# 15_-FPGA_Bank_8_Interface.net
KiCad netlist of a schematic drawn in Altium Designer
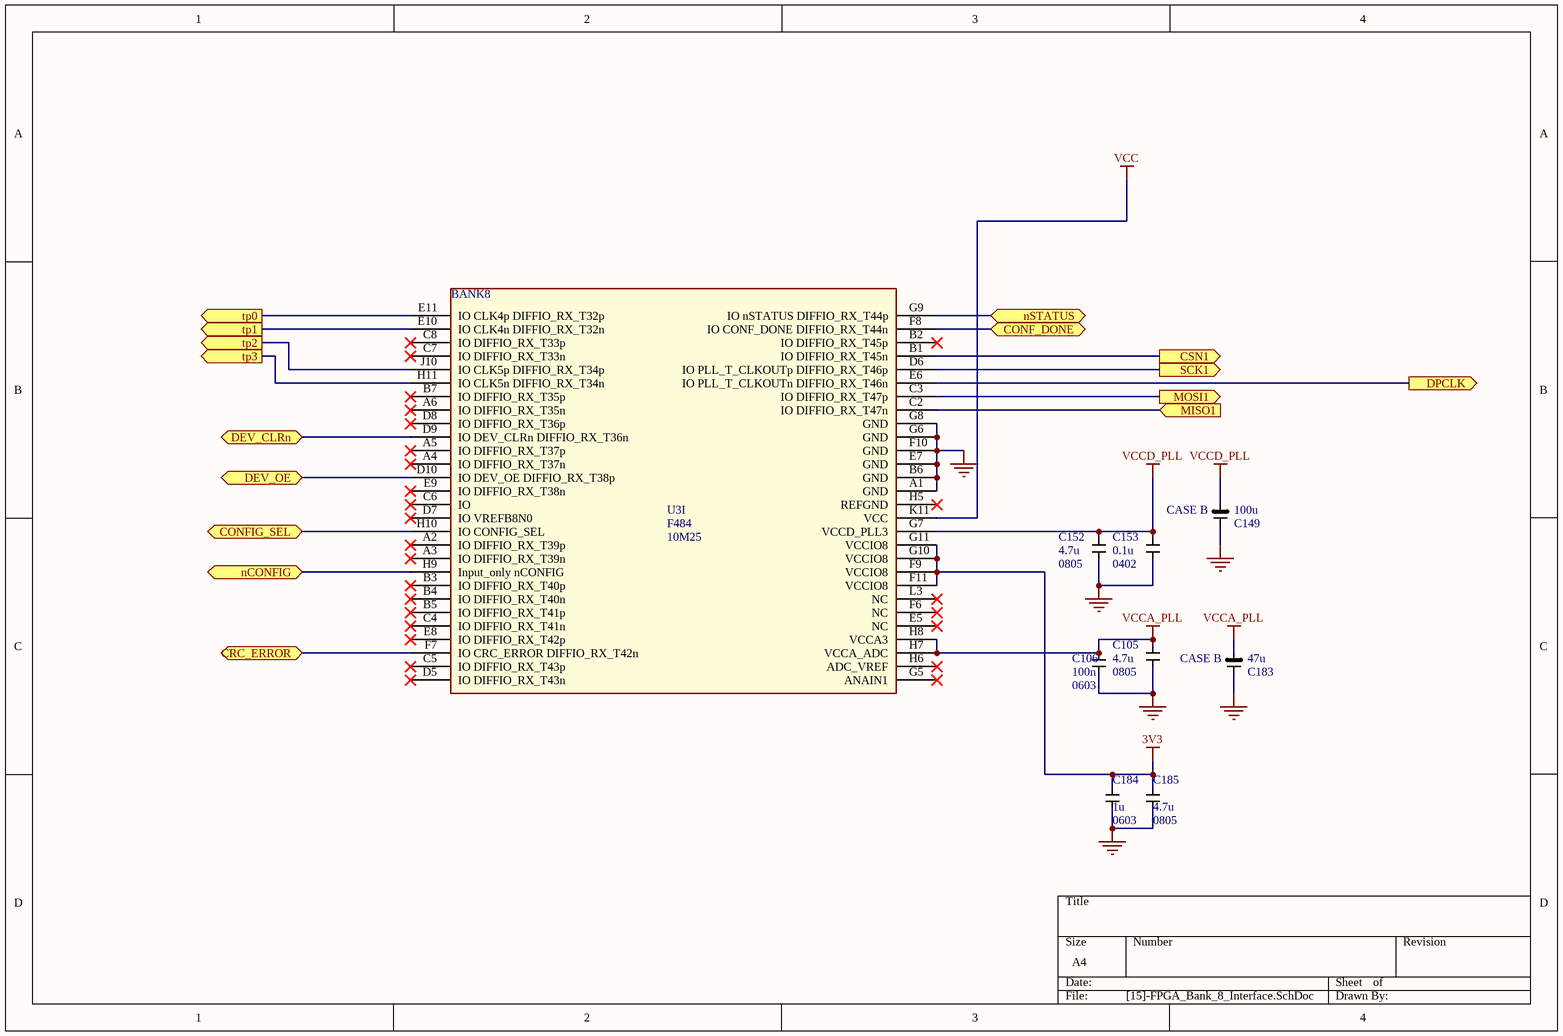
[diagram p0: [15]-FPGA_Bank_8_Interface.SchDoc]

(export (version "E")
  (design (tool "Eeschema 10.0.6"))
  (components
    (comp (ref "C105")
      (value "4.7u")
      (fields (field (name "PCB FOOTPRINT") "0805"))
      (libsource (lib "06031C104KAT2A") (part "Component_1"))
    )
    (comp (ref "C106")
      (value "100n")
      (footprint "*0603")
      (fields (field (name "PCB LAYER:") "0603"))
      (libsource (lib "0603YC105KAT2A") (part "Component_1"))
    )
    (comp (ref "C149")
      (value "100u")
      (footprint "CAPC3529X21N")
      (fields (field (name "CASE") "CASE B"))
      (libsource (lib "TAJB107K006TNJ") (part "Component_1"))
    )
    (comp (ref "C152")
      (value "4.7u")
      (fields (field (name "PCB FOOTPRINT") "0805"))
      (libsource (lib "06031C104KAT2A") (part "Component_1"))
    )
    (comp (ref "C153")
      (value "0.1u")
      (fields (field (name "PCB FOOTPRINT") "0402"))
      (libsource (lib "06031C104KAT2A") (part "Component_1"))
    )
    (comp (ref "C183")
      (value "47u")
      (footprint "CAPC3529X21N")
      (fields (field (name "CASE") "CASE B"))
      (libsource (lib "TAJB107K006TNJ") (part "Component_1"))
    )
    (comp (ref "C184")
      (value "1u")
      (footprint "*0603")
      (fields (field (name "PCB LAYER:") "0603"))
      (libsource (lib "0603YC105KAT2A") (part "Component_1"))
    )
    (comp (ref "C185")
      (value "4.7u")
      (footprint "*CAPC2013X140N")
      (fields (field (name "PCB PACKAGE") "0805"))
      (libsource (lib "08053D475KAT2A") (part "Component_1"))
    )
    (comp (ref "U3")
      (value "10M25")
      (footprint "*BGA484C100P22X22_2300X2300X200N")
      (fields (field (name "PART NO.") "10M25DAF484I7G") (field (name "PACKAGE TYPE") "F484"))
      (libsource (lib "10M25DAF484I7G") (part "Component_1"))
    )
  )
  (nets
    (net (code "1") (name "/CONFIG_SEL") (class "Default")
      (node (ref "U3") (pin "H10") (pinfunction "IO_CONFIG_SEL_H10") (pintype "passive"))
    )
    (net (code "2") (name "/CONF_DONE") (class "Default")
      (node (ref "U3") (pin "F8") (pinfunction "IO_CONF_DONE_DIFFIO_RX_T44n_F8") (pintype "passive"))
    )
    (net (code "3") (name "/CRC_ERROR") (class "Default")
      (node (ref "U3") (pin "F7") (pinfunction "IO_CRC_ERROR_DIFFIO_RX_T42n_F7") (pintype "passive"))
    )
    (net (code "4") (name "/CSN1") (class "Default")
      (node (ref "U3") (pin "B1") (pinfunction "IO_DIFFIO_RX_T45n_B1") (pintype "passive"))
    )
    (net (code "5") (name "/DEV_CLRn") (class "Default")
      (node (ref "U3") (pin "D9") (pinfunction "IO_DEV_CLRn_DIFFIO_RX_T36n_D9") (pintype "passive"))
    )
    (net (code "6") (name "/DEV_OE") (class "Default")
      (node (ref "U3") (pin "D10") (pinfunction "IO_DEV_OE_DIFFIO_RX_T38p_D10") (pintype "passive"))
    )
    (net (code "7") (name "/DPCLK") (class "Default")
      (node (ref "U3") (pin "E6") (pinfunction "IO_PLL_T_CLKOUTn_DIFFIO_RX_T46n_E6") (pintype "passive"))
    )
    (net (code "8") (name "/MISO1") (class "Default")
      (node (ref "U3") (pin "C2") (pinfunction "IO_DIFFIO_RX_T47n_C2") (pintype "passive"))
    )
    (net (code "9") (name "/MOSI1") (class "Default")
      (node (ref "U3") (pin "C3") (pinfunction "IO_DIFFIO_RX_T47p_C3") (pintype "passive"))
    )
    (net (code "10") (name "/SCK1") (class "Default")
      (node (ref "U3") (pin "D6") (pinfunction "IO_PLL_T_CLKOUTp_DIFFIO_RX_T46p_D6") (pintype "passive"))
    )
    (net (code "11") (name "/nCONFIG") (class "Default")
      (node (ref "U3") (pin "H9") (pinfunction "Input_only_nCONFIG_H9") (pintype "passive"))
    )
    (net (code "12") (name "/nSTATUS") (class "Default")
      (node (ref "U3") (pin "G9") (pinfunction "IO_nSTATUS_DIFFIO_RX_T44p_G9") (pintype "passive"))
    )
    (net (code "13") (name "/tp0") (class "Default")
      (node (ref "U3") (pin "E11") (pinfunction "IO_CLK4p_DIFFIO_RX_T32p_E11") (pintype "passive"))
    )
    (net (code "14") (name "/tp1") (class "Default")
      (node (ref "U3") (pin "E10") (pinfunction "IO_CLK4n_DIFFIO_RX_T32n_E10") (pintype "passive"))
    )
    (net (code "15") (name "/tp2") (class "Default")
      (node (ref "U3") (pin "J10") (pinfunction "IO_CLK5p_DIFFIO_RX_T34p_J10") (pintype "passive"))
    )
    (net (code "16") (name "/tp3") (class "Default")
      (node (ref "U3") (pin "H11") (pinfunction "IO_CLK5n_DIFFIO_RX_T34n_H11") (pintype "passive"))
    )
    (net (code "17") (name "3V3") (class "Default")
      (node (ref "C184") (pin "2") (pinfunction "2_2") (pintype "passive"))
      (node (ref "C185") (pin "2") (pinfunction "2_2") (pintype "passive"))
      (node (ref "U3") (pin "F11") (pinfunction "VCCIO8_F11") (pintype "passive"))
      (node (ref "U3") (pin "F9") (pinfunction "VCCIO8_F9") (pintype "passive"))
      (node (ref "U3") (pin "G10") (pinfunction "VCCIO8_G10") (pintype "passive"))
      (node (ref "U3") (pin "G11") (pinfunction "VCCIO8_G11") (pintype "passive"))
    )
    (net (code "18") (name "GND") (class "Default")
      (node (ref "C105") (pin "1") (pinfunction "1_1") (pintype "passive"))
      (node (ref "C106") (pin "1") (pinfunction "1_1") (pintype "passive"))
      (node (ref "C149") (pin "2") (pinfunction "2_2") (pintype "passive"))
      (node (ref "C152") (pin "1") (pinfunction "1_1") (pintype "passive"))
      (node (ref "C153") (pin "1") (pinfunction "1_1") (pintype "passive"))
      (node (ref "C183") (pin "2") (pinfunction "2_2") (pintype "passive"))
      (node (ref "C184") (pin "1") (pinfunction "1_1") (pintype "passive"))
      (node (ref "C185") (pin "1") (pinfunction "1_1") (pintype "passive"))
      (node (ref "U3") (pin "A1") (pinfunction "GND_A1") (pintype "passive"))
      (node (ref "U3") (pin "B6") (pinfunction "GND_B6") (pintype "passive"))
      (node (ref "U3") (pin "E7") (pinfunction "GND_E7") (pintype "passive"))
      (node (ref "U3") (pin "F10") (pinfunction "GND_F10") (pintype "passive"))
      (node (ref "U3") (pin "G6") (pinfunction "GND_G6") (pintype "passive"))
      (node (ref "U3") (pin "G8") (pinfunction "GND_G8") (pintype "passive"))
    )
    (net (code "19") (name "VCC") (class "Default")
      (node (ref "U3") (pin "K11") (pinfunction "VCC_K11") (pintype "passive"))
    )
    (net (code "20") (name "VCCA_PLL") (class "Default")
      (node (ref "C105") (pin "2") (pinfunction "2_2") (pintype "passive"))
      (node (ref "C106") (pin "2") (pinfunction "2_2") (pintype "passive"))
      (node (ref "C183") (pin "1") (pinfunction "1_1") (pintype "passive"))
      (node (ref "U3") (pin "H7") (pinfunction "VCCA_ADC_H7") (pintype "passive"))
      (node (ref "U3") (pin "H8") (pinfunction "VCCA3_H8") (pintype "passive"))
    )
    (net (code "21") (name "VCCD_PLL") (class "Default")
      (node (ref "C149") (pin "1") (pinfunction "1_1") (pintype "passive"))
      (node (ref "C152") (pin "2") (pinfunction "2_2") (pintype "passive"))
      (node (ref "C153") (pin "2") (pinfunction "2_2") (pintype "passive"))
      (node (ref "U3") (pin "G7") (pinfunction "VCCD_PLL3_G7") (pintype "passive"))
    )
    (net (code "22") (name "unconnected-(U3I-ADC_VREF-PadH6)") (class "Default")
      (node (ref "U3") (pin "H6") (pinfunction "ADC_VREF_H6") (pintype "passive+no_connect"))
    )
    (net (code "23") (name "unconnected-(U3I-ANAIN1-PadG5)") (class "Default")
      (node (ref "U3") (pin "G5") (pinfunction "ANAIN1_G5") (pintype "passive+no_connect"))
    )
    (net (code "24") (name "unconnected-(U3I-IO-PadC6)") (class "Default")
      (node (ref "U3") (pin "C6") (pinfunction "IO_C6") (pintype "passive+no_connect"))
    )
    (net (code "25") (name "unconnected-(U3I-IO_DIFFIO_RX_T33n-PadC7)") (class "Default")
      (node (ref "U3") (pin "C7") (pinfunction "IO_DIFFIO_RX_T33n_C7") (pintype "passive+no_connect"))
    )
    (net (code "26") (name "unconnected-(U3I-IO_DIFFIO_RX_T33p-PadC8)") (class "Default")
      (node (ref "U3") (pin "C8") (pinfunction "IO_DIFFIO_RX_T33p_C8") (pintype "passive+no_connect"))
    )
    (net (code "27") (name "unconnected-(U3I-IO_DIFFIO_RX_T35n-PadA6)") (class "Default")
      (node (ref "U3") (pin "A6") (pinfunction "IO_DIFFIO_RX_T35n_A6") (pintype "passive+no_connect"))
    )
    (net (code "28") (name "unconnected-(U3I-IO_DIFFIO_RX_T35p-PadB7)") (class "Default")
      (node (ref "U3") (pin "B7") (pinfunction "IO_DIFFIO_RX_T35p_B7") (pintype "passive+no_connect"))
    )
    (net (code "29") (name "unconnected-(U3I-IO_DIFFIO_RX_T36p-PadD8)") (class "Default")
      (node (ref "U3") (pin "D8") (pinfunction "IO_DIFFIO_RX_T36p_D8") (pintype "passive+no_connect"))
    )
    (net (code "30") (name "unconnected-(U3I-IO_DIFFIO_RX_T37n-PadA4)") (class "Default")
      (node (ref "U3") (pin "A4") (pinfunction "IO_DIFFIO_RX_T37n_A4") (pintype "passive+no_connect"))
    )
    (net (code "31") (name "unconnected-(U3I-IO_DIFFIO_RX_T37p-PadA5)") (class "Default")
      (node (ref "U3") (pin "A5") (pinfunction "IO_DIFFIO_RX_T37p_A5") (pintype "passive+no_connect"))
    )
    (net (code "32") (name "unconnected-(U3I-IO_DIFFIO_RX_T38n-PadE9)") (class "Default")
      (node (ref "U3") (pin "E9") (pinfunction "IO_DIFFIO_RX_T38n_E9") (pintype "passive+no_connect"))
    )
    (net (code "33") (name "unconnected-(U3I-IO_DIFFIO_RX_T39n-PadA3)") (class "Default")
      (node (ref "U3") (pin "A3") (pinfunction "IO_DIFFIO_RX_T39n_A3") (pintype "passive+no_connect"))
    )
    (net (code "34") (name "unconnected-(U3I-IO_DIFFIO_RX_T39p-PadA2)") (class "Default")
      (node (ref "U3") (pin "A2") (pinfunction "IO_DIFFIO_RX_T39p_A2") (pintype "passive+no_connect"))
    )
    (net (code "35") (name "unconnected-(U3I-IO_DIFFIO_RX_T40n-PadB4)") (class "Default")
      (node (ref "U3") (pin "B4") (pinfunction "IO_DIFFIO_RX_T40n_B4") (pintype "passive+no_connect"))
    )
    (net (code "36") (name "unconnected-(U3I-IO_DIFFIO_RX_T40p-PadB3)") (class "Default")
      (node (ref "U3") (pin "B3") (pinfunction "IO_DIFFIO_RX_T40p_B3") (pintype "passive+no_connect"))
    )
    (net (code "37") (name "unconnected-(U3I-IO_DIFFIO_RX_T41n-PadC4)") (class "Default")
      (node (ref "U3") (pin "C4") (pinfunction "IO_DIFFIO_RX_T41n_C4") (pintype "passive+no_connect"))
    )
    (net (code "38") (name "unconnected-(U3I-IO_DIFFIO_RX_T41p-PadB5)") (class "Default")
      (node (ref "U3") (pin "B5") (pinfunction "IO_DIFFIO_RX_T41p_B5") (pintype "passive+no_connect"))
    )
    (net (code "39") (name "unconnected-(U3I-IO_DIFFIO_RX_T42p-PadE8)") (class "Default")
      (node (ref "U3") (pin "E8") (pinfunction "IO_DIFFIO_RX_T42p_E8") (pintype "passive+no_connect"))
    )
    (net (code "40") (name "unconnected-(U3I-IO_DIFFIO_RX_T43n-PadD5)") (class "Default")
      (node (ref "U3") (pin "D5") (pinfunction "IO_DIFFIO_RX_T43n_D5") (pintype "passive+no_connect"))
    )
    (net (code "41") (name "unconnected-(U3I-IO_DIFFIO_RX_T43p-PadC5)") (class "Default")
      (node (ref "U3") (pin "C5") (pinfunction "IO_DIFFIO_RX_T43p_C5") (pintype "passive+no_connect"))
    )
    (net (code "42") (name "unconnected-(U3I-IO_DIFFIO_RX_T45p-PadB2)") (class "Default")
      (node (ref "U3") (pin "B2") (pinfunction "IO_DIFFIO_RX_T45p_B2") (pintype "passive+no_connect"))
    )
    (net (code "43") (name "unconnected-(U3I-IO_VREFB8N0-PadD7)") (class "Default")
      (node (ref "U3") (pin "D7") (pinfunction "IO_VREFB8N0_D7") (pintype "passive+no_connect"))
    )
    (net (code "44") (name "unconnected-(U3I-NC-PadE5)") (class "Default")
      (node (ref "U3") (pin "E5") (pinfunction "NC_E5") (pintype "passive+no_connect"))
    )
    (net (code "45") (name "unconnected-(U3I-NC-PadF6)") (class "Default")
      (node (ref "U3") (pin "F6") (pinfunction "NC_F6") (pintype "passive+no_connect"))
    )
    (net (code "46") (name "unconnected-(U3I-NC-PadL3)") (class "Default")
      (node (ref "U3") (pin "L3") (pinfunction "NC_L3") (pintype "passive+no_connect"))
    )
    (net (code "47") (name "unconnected-(U3I-REFGND-PadH5)") (class "Default")
      (node (ref "U3") (pin "H5") (pinfunction "REFGND_H5") (pintype "passive+no_connect"))
    )
  )
)
